# RoboSkin.net
KiCad netlist of a schematic drawn in EAGLE
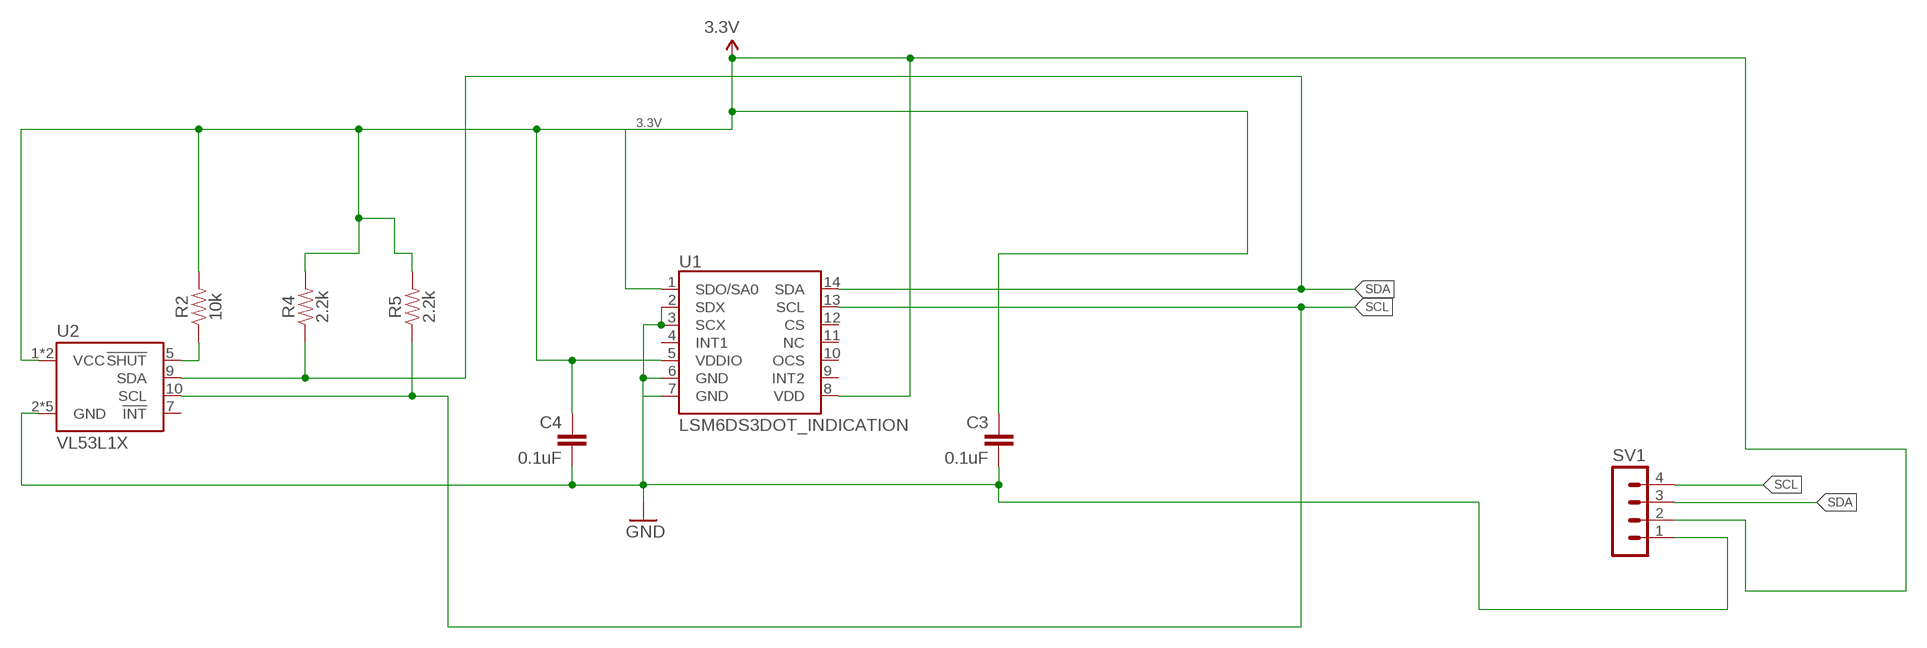
[diagram p0: schematic, sheet 1]

(export (version "E")
  (design (tool "Eeschema 10.0.6"))
  (components
    (comp (ref "C3")
      (value "0.1uF")
      (footprint "eagle-import:0603-CAP")
      (libsource (lib "eagle-import") (part "0.1UF-100V-10%(0603)"))
    )
    (comp (ref "C4")
      (value "0.1uF")
      (footprint "eagle-import:0603-CAP")
      (libsource (lib "eagle-import") (part "0.1UF-100V-10%(0603)"))
    )
    (comp (ref "R2")
      (value "10k")
      (footprint "eagle-import:0603")
      (libsource (lib "eagle-import") (part "10KOHM-0603-1/10W-1%"))
    )
    (comp (ref "R4")
      (value "2.2k")
      (footprint "eagle-import:0603")
      (libsource (lib "eagle-import") (part "2.2KOHM-0603-1/10W-1%"))
    )
    (comp (ref "R5")
      (value "2.2k")
      (footprint "eagle-import:0603")
      (libsource (lib "eagle-import") (part "2.2KOHM-0603-1/10W-1%"))
    )
    (comp (ref "SV1")
      (value "MA04-1")
      (footprint "eagle-import:MA04-1")
      (libsource (lib "eagle-import") (part "MA04-1"))
    )
    (comp (ref "U1")
      (value "LSM6DS3DOT_INDICATION")
      (footprint "eagle-import:LGA14L_DOT_INDICATOR")
      (libsource (lib "eagle-import") (part "LSM6DS3DOT_INDICATION"))
    )
    (comp (ref "U2")
      (value "VL53L1X")
      (footprint "eagle-import:VL53L1X")
      (libsource (lib "eagle-import") (part "VL53L1XSMD"))
    )
  )
  (nets
    (net (code "1") (name "3.3V") (class "Default")
      (node (ref "C3") (pin "1") (pinfunction "1_1") (pintype "passive"))
      (node (ref "C4") (pin "1") (pinfunction "1_1") (pintype "passive"))
      (node (ref "R2") (pin "2") (pinfunction "2_2") (pintype "passive"))
      (node (ref "R4") (pin "2") (pinfunction "2_2") (pintype "passive"))
      (node (ref "R5") (pin "2") (pinfunction "2_2") (pintype "passive"))
      (node (ref "SV1") (pin "2") (pinfunction "2_2") (pintype "passive"))
      (node (ref "U1") (pin "1") (pinfunction "SDO/SA0_1") (pintype "bidirectional"))
      (node (ref "U1") (pin "5") (pinfunction "VDDIO_5") (pintype "bidirectional"))
      (node (ref "U1") (pin "8") (pinfunction "VDD_8") (pintype "bidirectional"))
      (node (ref "U2") (pin "1") (pinfunction "VCC_1") (pintype "bidirectional"))
      (node (ref "U2") (pin "11") (pinfunction "VCC_11") (pintype "bidirectional"))
    )
    (net (code "2") (name "GND") (class "Default")
      (node (ref "C3") (pin "2") (pinfunction "2_2") (pintype "passive"))
      (node (ref "C4") (pin "2") (pinfunction "2_2") (pintype "passive"))
      (node (ref "SV1") (pin "1") (pinfunction "1_1") (pintype "passive"))
      (node (ref "U1") (pin "2") (pinfunction "SDX_2") (pintype "bidirectional"))
      (node (ref "U1") (pin "3") (pinfunction "SCX_3") (pintype "bidirectional"))
      (node (ref "U1") (pin "6") (pinfunction "GND_6") (pintype "bidirectional"))
      (node (ref "U1") (pin "7") (pinfunction "GND_7") (pintype "bidirectional"))
      (node (ref "U2") (pin "12") (pinfunction "GND_12") (pintype "bidirectional"))
      (node (ref "U2") (pin "2") (pinfunction "GND_2") (pintype "bidirectional"))
      (node (ref "U2") (pin "3") (pinfunction "GND_3") (pintype "bidirectional"))
      (node (ref "U2") (pin "4") (pinfunction "GND_4") (pintype "bidirectional"))
      (node (ref "U2") (pin "6") (pinfunction "GND_6") (pintype "bidirectional"))
    )
    (net (code "3") (name "Net-(U2-~{SHUT})") (class "Default")
      (node (ref "R2") (pin "1") (pinfunction "1_1") (pintype "passive"))
      (node (ref "U2") (pin "5") (pinfunction "~{SHUT}_5") (pintype "bidirectional"))
    )
    (net (code "4") (name "SCL") (class "Default")
      (node (ref "R5") (pin "1") (pinfunction "1_1") (pintype "passive"))
      (node (ref "SV1") (pin "4") (pinfunction "4_4") (pintype "passive"))
      (node (ref "U1") (pin "13") (pinfunction "SCL_13") (pintype "bidirectional"))
      (node (ref "U2") (pin "10") (pinfunction "SCL_10") (pintype "bidirectional"))
    )
    (net (code "5") (name "SDA") (class "Default")
      (node (ref "R4") (pin "1") (pinfunction "1_1") (pintype "passive"))
      (node (ref "SV1") (pin "3") (pinfunction "3_3") (pintype "passive"))
      (node (ref "U1") (pin "14") (pinfunction "SDA_14") (pintype "bidirectional"))
      (node (ref "U2") (pin "9") (pinfunction "SDA_9") (pintype "bidirectional"))
    )
    (net (code "6") (name "unconnected-(U1-CS-Pad12)") (class "Default")
      (node (ref "U1") (pin "12") (pinfunction "CS_12") (pintype "bidirectional"))
    )
    (net (code "7") (name "unconnected-(U1-INT1-Pad4)") (class "Default")
      (node (ref "U1") (pin "4") (pinfunction "INT1_4") (pintype "bidirectional"))
    )
    (net (code "8") (name "unconnected-(U1-INT2-Pad9)") (class "Default")
      (node (ref "U1") (pin "9") (pinfunction "INT2_9") (pintype "bidirectional"))
    )
    (net (code "9") (name "unconnected-(U1-NC-Pad11)") (class "Default")
      (node (ref "U1") (pin "11") (pinfunction "NC_11") (pintype "bidirectional"))
    )
    (net (code "10") (name "unconnected-(U1-OCS-Pad10)") (class "Default")
      (node (ref "U1") (pin "10") (pinfunction "OCS_10") (pintype "bidirectional"))
    )
    (net (code "11") (name "unconnected-(U2-~{INT}-Pad7)") (class "Default")
      (node (ref "U2") (pin "7") (pinfunction "~{INT}_7") (pintype "bidirectional"))
    )
  )
)
